# Interface.net
KiCad netlist of a schematic drawn in EAGLE
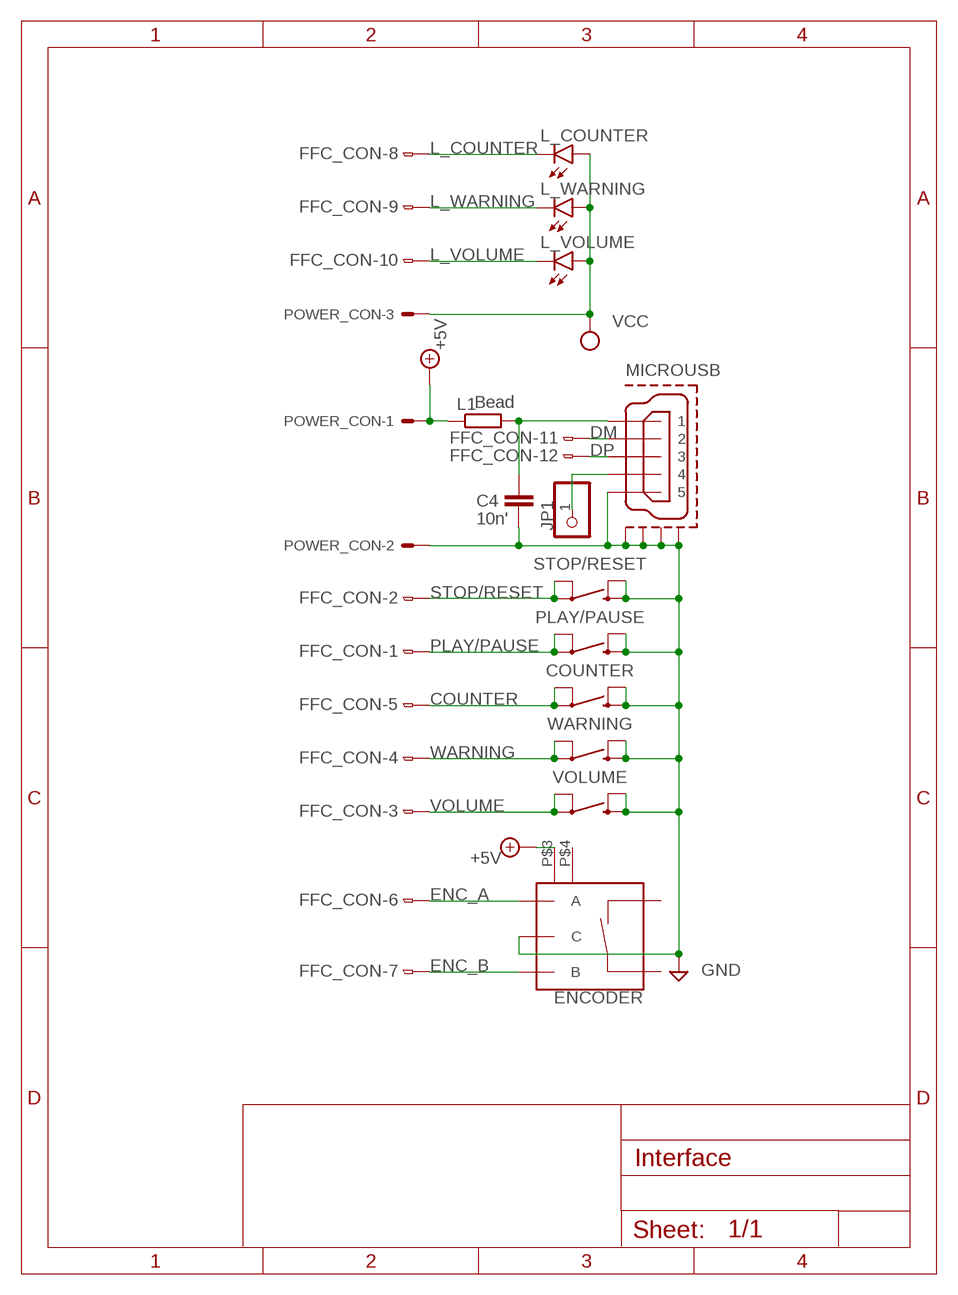
[diagram p0: schematic, sheet 1]

(export (version "E")
  (design (tool "Eeschema 10.0.6"))
  (components
    (comp (ref "C4")
      (value "10n'")
      (footprint "eagle-import:C0402")
      (libsource (lib "eagle-import") (part "C-EUC0402"))
    )
    (comp (ref "COUNTER")
      (value "MOMENTARY-SWITCH-SPST-PTH-12MM")
      (footprint "eagle-import:TACTILE_SWITCH_PTH_12MM")
      (libsource (lib "eagle-import") (part "MOMENTARY-SWITCH-SPST-PTH-12MM"))
    )
    (comp (ref "ENCODER")
      (value "ENCODER-SWITCH")
      (footprint "eagle-import:ROTARY_ENC_PLAIN")
      (libsource (lib "eagle-import") (part "ENCODER-SWITCH"))
    )
    (comp (ref "FFC_CON")
      (value "FH12-12S-0.5S_THINNER")
      (footprint "eagle-import:FH12-12S-0.5SH_THINER")
      (libsource (lib "eagle-import") (part "FH12-12S-0.5S_THINNER"))
    )
    (comp (ref "JP1")
      (value "PINHD-1X1")
      (footprint "eagle-import:1X01")
      (libsource (lib "eagle-import") (part "PINHD-1X1"))
    )
    (comp (ref "L1")
      (value "Bead")
      (footprint "eagle-import:R0603")
      (libsource (lib "eagle-import") (part "R-EU_R0603"))
    )
    (comp (ref "L_COUNTER")
      (value "LEDCHIPLED_0805")
      (footprint "eagle-import:CHIPLED_0805")
      (libsource (lib "eagle-import") (part "LEDCHIPLED_0805"))
    )
    (comp (ref "L_VOLUME")
      (value "LEDCHIPLED_0805")
      (footprint "eagle-import:CHIPLED_0805")
      (libsource (lib "eagle-import") (part "LEDCHIPLED_0805"))
    )
    (comp (ref "L_WARNING")
      (value "LEDCHIPLED_0805")
      (footprint "eagle-import:CHIPLED_0805")
      (libsource (lib "eagle-import") (part "LEDCHIPLED_0805"))
    )
    (comp (ref "MICROUSB")
      (value "MICRO-USB-RECEPTACLE")
      (footprint "eagle-import:47589-0002")
      (libsource (lib "eagle-import") (part "MICRO-USB-RECEPTACLE"))
    )
    (comp (ref "PLAY/PAUSE")
      (value "MOMENTARY-SWITCH-SPST-PTH-12MM")
      (footprint "eagle-import:TACTILE_SWITCH_PTH_12MM")
      (libsource (lib "eagle-import") (part "MOMENTARY-SWITCH-SPST-PTH-12MM"))
    )
    (comp (ref "POWER_CON")
      (value "JST-XH-03-PIN-LONG-PAD")
      (footprint "eagle-import:JST-XH-03-PACKAGE-LONG-PAD")
      (libsource (lib "eagle-import") (part "JST-XH-03-PIN-LONG-PAD"))
    )
    (comp (ref "STOP/RESET")
      (value "MOMENTARY-SWITCH-SPST-PTH-12MM")
      (footprint "eagle-import:TACTILE_SWITCH_PTH_12MM")
      (libsource (lib "eagle-import") (part "MOMENTARY-SWITCH-SPST-PTH-12MM"))
    )
    (comp (ref "VOLUME")
      (value "MOMENTARY-SWITCH-SPST-PTH-12MM")
      (footprint "eagle-import:TACTILE_SWITCH_PTH_12MM")
      (libsource (lib "eagle-import") (part "MOMENTARY-SWITCH-SPST-PTH-12MM"))
    )
    (comp (ref "WARNING")
      (value "MOMENTARY-SWITCH-SPST-PTH-12MM")
      (footprint "eagle-import:TACTILE_SWITCH_PTH_12MM")
      (libsource (lib "eagle-import") (part "MOMENTARY-SWITCH-SPST-PTH-12MM"))
    )
  )
  (nets
    (net (code "1") (name "+5V") (class "Default")
      (node (ref "ENCODER") (pin "P$3") (pinfunction "GND1_P$3") (pintype "bidirectional"))
      (node (ref "L1") (pin "1") (pinfunction "1_1") (pintype "passive"))
      (node (ref "POWER_CON") (pin "1") (pinfunction "S_1") (pintype "passive"))
    )
    (net (code "2") (name "/COUNTER") (class "Default")
      (node (ref "COUNTER") (pin "1") (pinfunction "1_1") (pintype "passive"))
      (node (ref "COUNTER") (pin "2") (pinfunction "3_2") (pintype "passive"))
      (node (ref "FFC_CON") (pin "5") (pinfunction "1_5") (pintype "passive"))
    )
    (net (code "3") (name "/DM") (class "Default")
      (node (ref "FFC_CON") (pin "11") (pinfunction "1_11") (pintype "passive"))
      (node (ref "MICROUSB") (pin "2") (pinfunction "2_2") (pintype "input"))
    )
    (net (code "4") (name "/DP") (class "Default")
      (node (ref "FFC_CON") (pin "12") (pinfunction "1_12") (pintype "passive"))
      (node (ref "MICROUSB") (pin "3") (pinfunction "3_3") (pintype "input"))
    )
    (net (code "5") (name "/ENC_A") (class "Default")
      (node (ref "ENCODER") (pin "A") (pinfunction "A_A") (pintype "bidirectional"))
      (node (ref "FFC_CON") (pin "6") (pinfunction "1_6") (pintype "passive"))
    )
    (net (code "6") (name "/ENC_B") (class "Default")
      (node (ref "ENCODER") (pin "B") (pinfunction "B_B") (pintype "bidirectional"))
      (node (ref "FFC_CON") (pin "7") (pinfunction "1_7") (pintype "passive"))
    )
    (net (code "7") (name "/L_COUNTER") (class "Default")
      (node (ref "FFC_CON") (pin "8") (pinfunction "1_8") (pintype "passive"))
      (node (ref "L_COUNTER") (pin "C") (pinfunction "C_C") (pintype "passive"))
    )
    (net (code "8") (name "/L_VOLUME") (class "Default")
      (node (ref "FFC_CON") (pin "10") (pinfunction "1_10") (pintype "passive"))
      (node (ref "L_VOLUME") (pin "C") (pinfunction "C_C") (pintype "passive"))
    )
    (net (code "9") (name "/L_WARNING") (class "Default")
      (node (ref "FFC_CON") (pin "9") (pinfunction "1_9") (pintype "passive"))
      (node (ref "L_WARNING") (pin "C") (pinfunction "C_C") (pintype "passive"))
    )
    (net (code "10") (name "/PLAY{slash}PAUSE") (class "Default")
      (node (ref "FFC_CON") (pin "1") (pinfunction "1_1") (pintype "passive"))
      (node (ref "PLAY/PAUSE") (pin "1") (pinfunction "1_1") (pintype "passive"))
      (node (ref "PLAY/PAUSE") (pin "2") (pinfunction "3_2") (pintype "passive"))
    )
    (net (code "11") (name "/STOP{slash}RESET") (class "Default")
      (node (ref "FFC_CON") (pin "2") (pinfunction "1_2") (pintype "passive"))
      (node (ref "STOP/RESET") (pin "1") (pinfunction "1_1") (pintype "passive"))
      (node (ref "STOP/RESET") (pin "2") (pinfunction "3_2") (pintype "passive"))
    )
    (net (code "12") (name "/VOLUME") (class "Default")
      (node (ref "FFC_CON") (pin "3") (pinfunction "1_3") (pintype "passive"))
      (node (ref "VOLUME") (pin "1") (pinfunction "1_1") (pintype "passive"))
      (node (ref "VOLUME") (pin "2") (pinfunction "3_2") (pintype "passive"))
    )
    (net (code "13") (name "/WARNING") (class "Default")
      (node (ref "FFC_CON") (pin "4") (pinfunction "1_4") (pintype "passive"))
      (node (ref "WARNING") (pin "1") (pinfunction "1_1") (pintype "passive"))
      (node (ref "WARNING") (pin "2") (pinfunction "3_2") (pintype "passive"))
    )
    (net (code "14") (name "GND") (class "Default")
      (node (ref "C4") (pin "2") (pinfunction "2_2") (pintype "passive"))
      (node (ref "COUNTER") (pin "3") (pinfunction "2_3") (pintype "passive"))
      (node (ref "COUNTER") (pin "4") (pinfunction "4_4") (pintype "passive"))
      (node (ref "ENCODER") (pin "C") (pinfunction "C_C") (pintype "bidirectional"))
      (node (ref "MICROUSB") (pin "5") (pinfunction "5_5") (pintype "input"))
      (node (ref "MICROUSB") (pin "CASING1") (pinfunction "GND1_CASING1") (pintype "bidirectional"))
      (node (ref "MICROUSB") (pin "CASING2") (pinfunction "GND2_CASING2") (pintype "bidirectional"))
      (node (ref "MICROUSB") (pin "CASING3") (pinfunction "GND3_CASING3") (pintype "bidirectional"))
      (node (ref "MICROUSB") (pin "CASING4") (pinfunction "GND4_CASING4") (pintype "bidirectional"))
      (node (ref "PLAY/PAUSE") (pin "3") (pinfunction "2_3") (pintype "passive"))
      (node (ref "PLAY/PAUSE") (pin "4") (pinfunction "4_4") (pintype "passive"))
      (node (ref "POWER_CON") (pin "2") (pinfunction "S_2") (pintype "passive"))
      (node (ref "STOP/RESET") (pin "3") (pinfunction "2_3") (pintype "passive"))
      (node (ref "STOP/RESET") (pin "4") (pinfunction "4_4") (pintype "passive"))
      (node (ref "VOLUME") (pin "3") (pinfunction "2_3") (pintype "passive"))
      (node (ref "VOLUME") (pin "4") (pinfunction "4_4") (pintype "passive"))
      (node (ref "WARNING") (pin "3") (pinfunction "2_3") (pintype "passive"))
      (node (ref "WARNING") (pin "4") (pinfunction "4_4") (pintype "passive"))
    )
    (net (code "15") (name "Net-(C4-Pad1)") (class "Default")
      (node (ref "C4") (pin "1") (pinfunction "1_1") (pintype "passive"))
      (node (ref "L1") (pin "2") (pinfunction "2_2") (pintype "passive"))
      (node (ref "MICROUSB") (pin "1") (pinfunction "1_1") (pintype "input"))
    )
    (net (code "16") (name "Net-(JP1-Pad1)") (class "Default")
      (node (ref "JP1") (pin "1") (pinfunction "1_1") (pintype "passive"))
      (node (ref "MICROUSB") (pin "4") (pinfunction "4_4") (pintype "input"))
    )
    (net (code "17") (name "VCC") (class "Default")
      (node (ref "L_COUNTER") (pin "A") (pinfunction "A_A") (pintype "passive"))
      (node (ref "L_VOLUME") (pin "A") (pinfunction "A_A") (pintype "passive"))
      (node (ref "L_WARNING") (pin "A") (pinfunction "A_A") (pintype "passive"))
      (node (ref "POWER_CON") (pin "3") (pinfunction "S_3") (pintype "passive"))
    )
    (net (code "18") (name "unconnected-(ENCODER-GND2-PadP$4)") (class "Default")
      (node (ref "ENCODER") (pin "P$4") (pinfunction "GND2_P$4") (pintype "bidirectional"))
    )
    (net (code "19") (name "unconnected-(ENCODER-PadSW+)") (class "Default")
      (node (ref "ENCODER") (pin "SW+") (pinfunction "SW+_SW+") (pintype "bidirectional"))
    )
    (net (code "20") (name "unconnected-(ENCODER-PadSW-)") (class "Default")
      (node (ref "ENCODER") (pin "SW-") (pinfunction "SW-_SW-") (pintype "bidirectional"))
    )
  )
)
